# PowerAdapterBoard.net
KiCad netlist of a schematic drawn in EAGLE
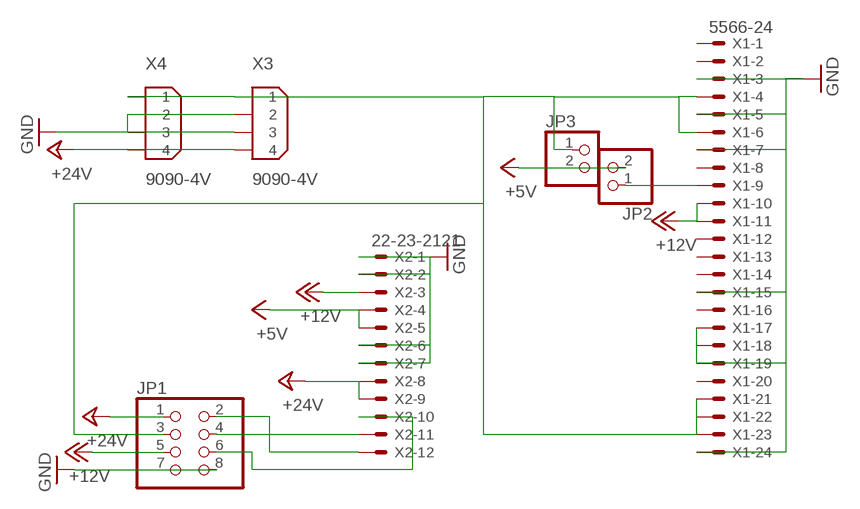
[diagram p0: schematic, sheet 1]

(export (version "E")
  (design (tool "Eeschema 10.0.6"))
  (components
    (comp (ref "JP1")
      (value "PINHD-2X4")
      (footprint "eagle-import:2X04")
      (libsource (lib "eagle-import") (part "PINHD-2X4"))
    )
    (comp (ref "JP2")
      (value "PINHD-1X2")
      (footprint "eagle-import:1X02")
      (libsource (lib "eagle-import") (part "PINHD-1X2"))
    )
    (comp (ref "JP3")
      (value "PINHD-1X2")
      (footprint "eagle-import:1X02")
      (libsource (lib "eagle-import") (part "PINHD-1X2"))
    )
    (comp (ref "X1")
      (value "5566-24")
      (footprint "eagle-import:5566-24")
      (libsource (lib "eagle-import") (part "5566-24"))
    )
    (comp (ref "X2")
      (value "22-23-2121")
      (footprint "eagle-import:22-23-2121")
      (fields (field (name "MF") "MOLEX"))
      (libsource (lib "eagle-import") (part "22-23-2121"))
    )
    (comp (ref "X3")
      (value "9090-4V")
      (footprint "eagle-import:9090-4V")
      (libsource (lib "eagle-import") (part "9090-4V"))
    )
    (comp (ref "X4")
      (value "9090-4V")
      (footprint "eagle-import:9090-4V")
      (libsource (lib "eagle-import") (part "9090-4V"))
    )
  )
  (nets
    (net (code "1") (name "+5V") (class "Default")
      (node (ref "JP2") (pin "2") (pinfunction "2_2") (pintype "passive"))
      (node (ref "JP3") (pin "2") (pinfunction "2_2") (pintype "passive"))
      (node (ref "X2") (pin "4") (pinfunction "S_4") (pintype "passive"))
      (node (ref "X2") (pin "5") (pinfunction "S_5") (pintype "passive"))
    )
    (net (code "2") (name "+12V") (class "Default")
      (node (ref "JP1") (pin "5") (pinfunction "5_5") (pintype "passive"))
      (node (ref "X1") (pin "10") (pinfunction "S_10") (pintype "passive"))
      (node (ref "X1") (pin "11") (pinfunction "S_11") (pintype "passive"))
      (node (ref "X2") (pin "3") (pinfunction "S_3") (pintype "passive"))
    )
    (net (code "3") (name "+24V") (class "Default")
      (node (ref "JP1") (pin "1") (pinfunction "1_1") (pintype "passive"))
      (node (ref "X2") (pin "8") (pinfunction "S_8") (pintype "passive"))
      (node (ref "X2") (pin "9") (pinfunction "S_9") (pintype "passive"))
      (node (ref "X3") (pin "4") (pinfunction "4_4") (pintype "passive"))
      (node (ref "X4") (pin "4") (pinfunction "4_4") (pintype "passive"))
    )
    (net (code "4") (name "GND") (class "Default")
      (node (ref "JP1") (pin "7") (pinfunction "7_7") (pintype "passive"))
      (node (ref "JP1") (pin "8") (pinfunction "8_8") (pintype "passive"))
      (node (ref "X1") (pin "15") (pinfunction "S_15") (pintype "passive"))
      (node (ref "X1") (pin "17") (pinfunction "S_17") (pintype "passive"))
      (node (ref "X1") (pin "18") (pinfunction "S_18") (pintype "passive"))
      (node (ref "X1") (pin "19") (pinfunction "S_19") (pintype "passive"))
      (node (ref "X1") (pin "24") (pinfunction "S_24") (pintype "passive"))
      (node (ref "X1") (pin "3") (pinfunction "S_3") (pintype "passive"))
      (node (ref "X1") (pin "5") (pinfunction "S_5") (pintype "passive"))
      (node (ref "X1") (pin "7") (pinfunction "S_7") (pintype "passive"))
      (node (ref "X2") (pin "1") (pinfunction "S_1") (pintype "passive"))
      (node (ref "X2") (pin "2") (pinfunction "S_2") (pintype "passive"))
      (node (ref "X2") (pin "6") (pinfunction "S_6") (pintype "passive"))
      (node (ref "X2") (pin "7") (pinfunction "S_7") (pintype "passive"))
      (node (ref "X3") (pin "2") (pinfunction "2_2") (pintype "passive"))
      (node (ref "X3") (pin "3") (pinfunction "3_3") (pintype "passive"))
      (node (ref "X4") (pin "2") (pinfunction "2_2") (pintype "passive"))
      (node (ref "X4") (pin "3") (pinfunction "3_3") (pintype "passive"))
    )
    (net (code "5") (name "Net-(X1N-S)") (class "Default")
      (node (ref "JP1") (pin "3") (pinfunction "3_3") (pintype "passive"))
      (node (ref "JP3") (pin "1") (pinfunction "1_1") (pintype "passive"))
      (node (ref "X1") (pin "21") (pinfunction "S_21") (pintype "passive"))
      (node (ref "X1") (pin "22") (pinfunction "S_22") (pintype "passive"))
      (node (ref "X1") (pin "23") (pinfunction "S_23") (pintype "passive"))
      (node (ref "X1") (pin "4") (pinfunction "S_4") (pintype "passive"))
      (node (ref "X1") (pin "6") (pinfunction "S_6") (pintype "passive"))
      (node (ref "X3") (pin "1") (pinfunction "1_1") (pintype "passive"))
      (node (ref "X4") (pin "1") (pinfunction "1_1") (pintype "passive"))
    )
    (net (code "6") (name "Net-(X1X-S)") (class "Default")
      (node (ref "JP2") (pin "1") (pinfunction "1_1") (pintype "passive"))
      (node (ref "X1") (pin "9") (pinfunction "S_9") (pintype "passive"))
    )
    (net (code "7") (name "Net-(X2B-S)") (class "Default")
      (node (ref "JP1") (pin "6") (pinfunction "6_6") (pintype "passive"))
      (node (ref "X2") (pin "10") (pinfunction "S_10") (pintype "passive"))
    )
    (net (code "8") (name "Net-(X2C-S)") (class "Default")
      (node (ref "JP1") (pin "4") (pinfunction "4_4") (pintype "passive"))
      (node (ref "X2") (pin "11") (pinfunction "S_11") (pintype "passive"))
    )
    (net (code "9") (name "Net-(X2D-S)") (class "Default")
      (node (ref "JP1") (pin "2") (pinfunction "2_2") (pintype "passive"))
      (node (ref "X2") (pin "12") (pinfunction "S_12") (pintype "passive"))
    )
    (net (code "10") (name "unconnected-(X1A-S-Pad1)") (class "Default")
      (node (ref "X1") (pin "1") (pinfunction "S_1") (pintype "passive"))
    )
    (net (code "11") (name "unconnected-(X1D-S-Pad12)") (class "Default")
      (node (ref "X1") (pin "12") (pinfunction "S_12") (pintype "passive"))
    )
    (net (code "12") (name "unconnected-(X1E-S-Pad13)") (class "Default")
      (node (ref "X1") (pin "13") (pinfunction "S_13") (pintype "passive"))
    )
    (net (code "13") (name "unconnected-(X1F-S-Pad14)") (class "Default")
      (node (ref "X1") (pin "14") (pinfunction "S_14") (pintype "passive"))
    )
    (net (code "14") (name "unconnected-(X1H-S-Pad16)") (class "Default")
      (node (ref "X1") (pin "16") (pinfunction "S_16") (pintype "passive"))
    )
    (net (code "15") (name "unconnected-(X1L-S-Pad2)") (class "Default")
      (node (ref "X1") (pin "2") (pinfunction "S_2") (pintype "passive"))
    )
    (net (code "16") (name "unconnected-(X1M-S-Pad20)") (class "Default")
      (node (ref "X1") (pin "20") (pinfunction "S_20") (pintype "passive"))
    )
    (net (code "17") (name "unconnected-(X1W-S-Pad8)") (class "Default")
      (node (ref "X1") (pin "8") (pinfunction "S_8") (pintype "passive"))
    )
  )
)
